# GPS_Tracker_V3.net
KiCad netlist of a schematic drawn in EAGLE
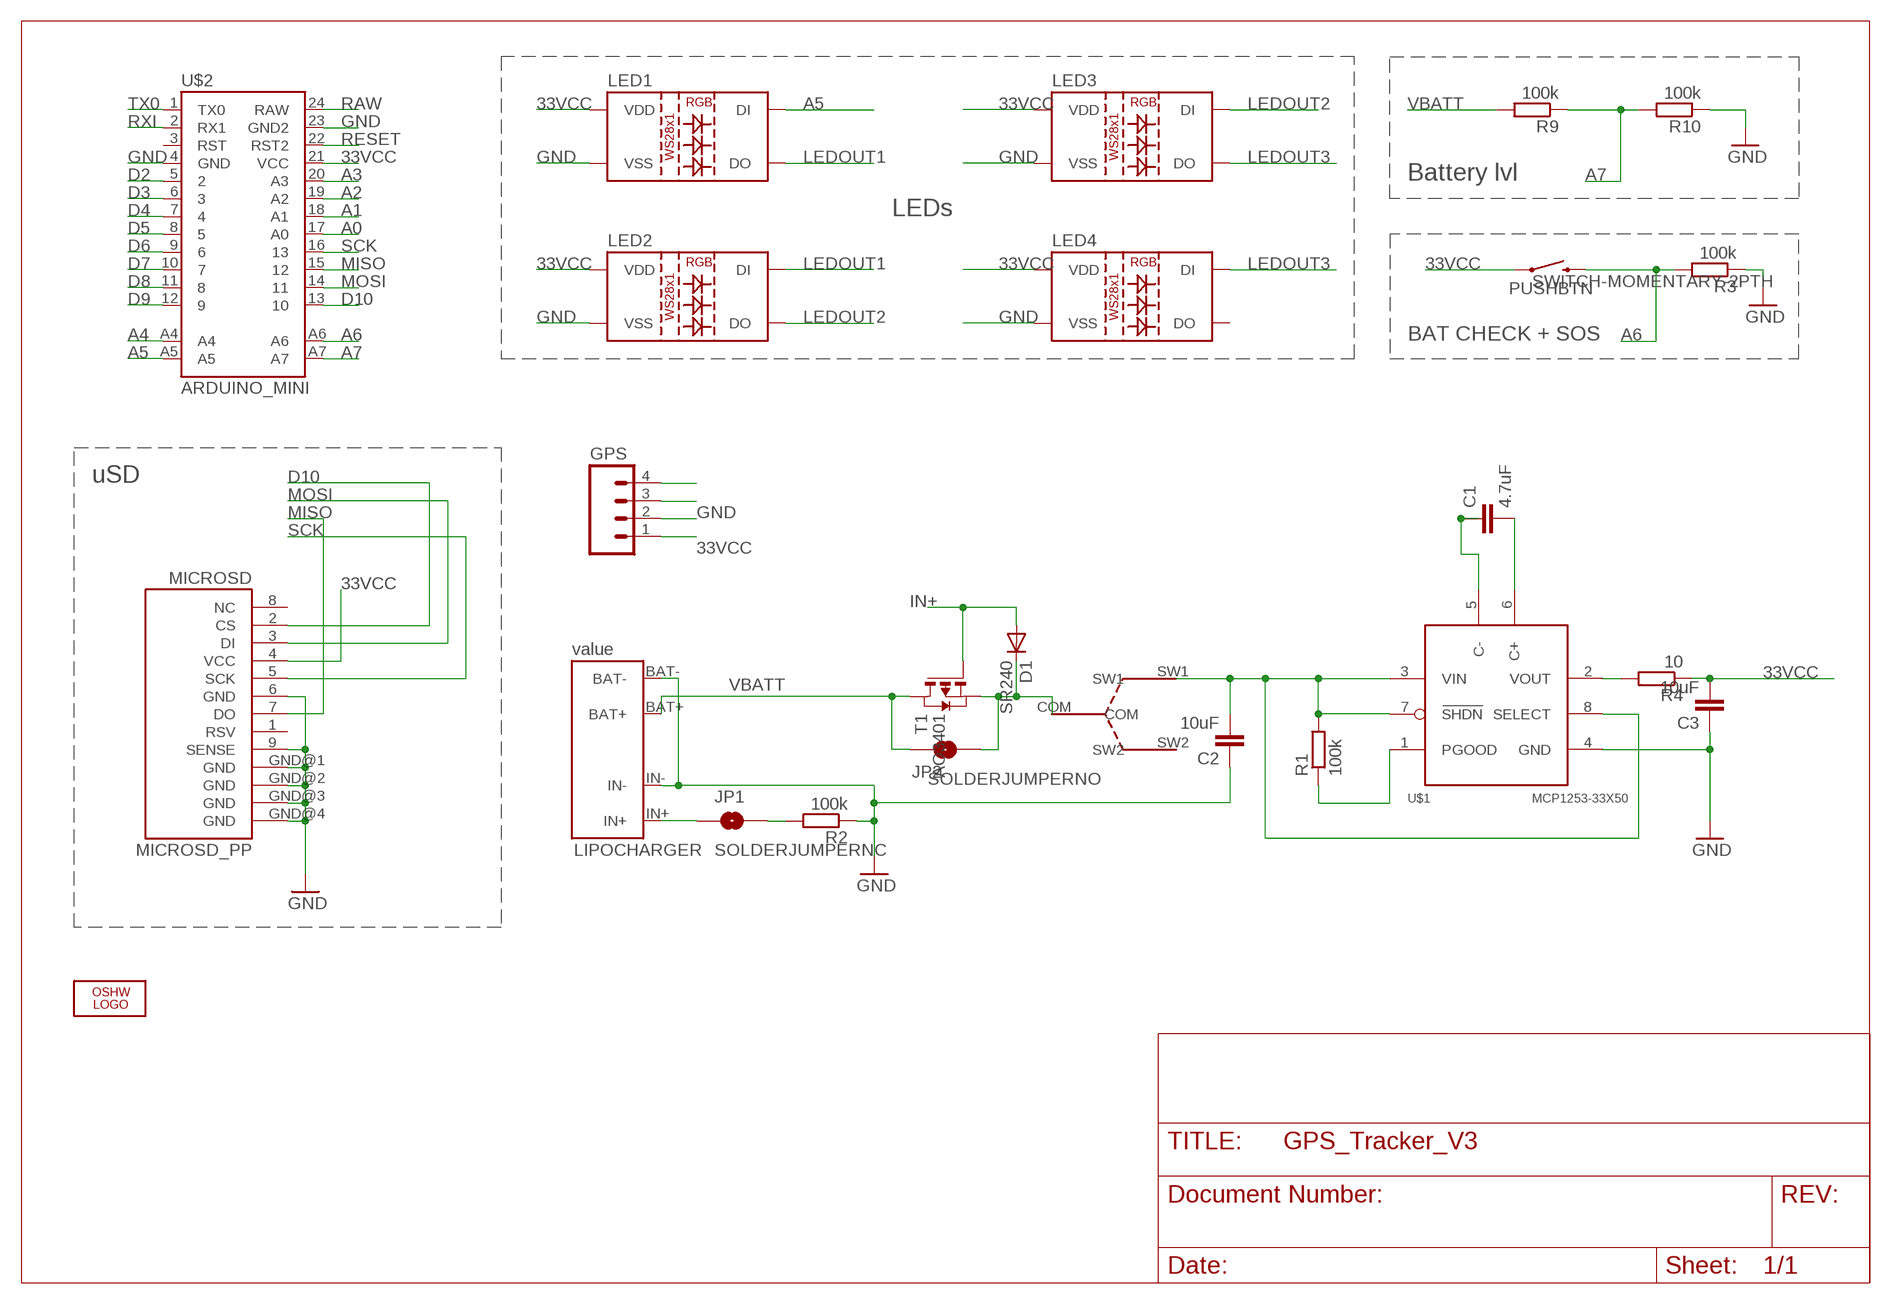
[diagram p0: schematic, sheet 1]

(export (version "E")
  (design (tool "Eeschema 10.0.6"))
  (components
    (comp (ref "C1")
      (value "4.7uF")
      (footprint "eagle-import:C1206")
      (libsource (lib "eagle-import") (part "C-EUC1206"))
    )
    (comp (ref "C2")
      (value "10uF")
      (footprint "eagle-import:C1206")
      (libsource (lib "eagle-import") (part "C-EUC1206"))
    )
    (comp (ref "C3")
      (value "10uF")
      (footprint "eagle-import:C1206")
      (libsource (lib "eagle-import") (part "C-EUC1206"))
    )
    (comp (ref "D1")
      (value "SR240")
      (footprint "eagle-import:DO214AC")
      (libsource (lib "eagle-import") (part "DIODE-DO214AC"))
    )
    (comp (ref "GPS")
      (value "M04PTH")
      (footprint "eagle-import:1X04")
      (libsource (lib "eagle-import") (part "M04PTH"))
    )
    (comp (ref "JP1")
      (value "SOLDERJUMPERNC")
      (footprint "eagle-import:SJ_2S")
      (libsource (lib "eagle-import") (part "SOLDERJUMPERNC"))
    )
    (comp (ref "JP2")
      (value "SOLDERJUMPERNO")
      (footprint "eagle-import:SJ_2S-NO")
      (libsource (lib "eagle-import") (part "SOLDERJUMPERNO"))
    )
    (comp (ref "LED1")
      (value "LED-TRICOLOR-5050-ICWS2811")
      (footprint "eagle-import:LED-TRICOLOR-5050-IC")
      (libsource (lib "eagle-import") (part "LED-TRICOLOR-5050-ICWS2811"))
    )
    (comp (ref "LED2")
      (value "LED-TRICOLOR-5050-ICWS2811")
      (footprint "eagle-import:LED-TRICOLOR-5050-IC")
      (libsource (lib "eagle-import") (part "LED-TRICOLOR-5050-ICWS2811"))
    )
    (comp (ref "LED3")
      (value "LED-TRICOLOR-5050-ICWS2811")
      (footprint "eagle-import:LED-TRICOLOR-5050-IC")
      (libsource (lib "eagle-import") (part "LED-TRICOLOR-5050-ICWS2811"))
    )
    (comp (ref "LED4")
      (value "LED-TRICOLOR-5050-ICWS2811")
      (footprint "eagle-import:LED-TRICOLOR-5050-IC")
      (libsource (lib "eagle-import") (part "LED-TRICOLOR-5050-ICWS2811"))
    )
    (comp (ref "LIPOCHARGER")
      (value "LIPO_CHARGER")
      (footprint "eagle-import:LIPO_CHARGER")
      (libsource (lib "eagle-import") (part "LIPO_CHARGER"))
    )
    (comp (ref "LOGO1")
      (value "OSHW_LOGO_10MILX0200-NT")
      (footprint "eagle-import:OSHW_10X200_NOTEXT")
      (libsource (lib "eagle-import") (part "OSHW_LOGO_10MILX0200-NT"))
    )
    (comp (ref "MICROSD")
      (value "MICROSD_PP")
      (footprint "eagle-import:MICROSD_PP")
      (libsource (lib "eagle-import") (part "MICROSD_PP"))
    )
    (comp (ref "PUSHBTN")
      (value "SWITCH-MOMENTARY-2PTH")
      (footprint "eagle-import:TACTILE-PTH")
      (libsource (lib "eagle-import") (part "SWITCH-MOMENTARY-2PTH"))
    )
    (comp (ref "R1")
      (value "100k")
      (footprint "eagle-import:R1206")
      (libsource (lib "eagle-import") (part "R-EU_R1206"))
    )
    (comp (ref "R2")
      (value "100k")
      (footprint "eagle-import:R1206")
      (libsource (lib "eagle-import") (part "R-EU_R1206"))
    )
    (comp (ref "R3")
      (value "100k")
      (footprint "eagle-import:R1206")
      (libsource (lib "eagle-import") (part "R-EU_R1206"))
    )
    (comp (ref "R4")
      (value "10")
      (footprint "eagle-import:R1206")
      (libsource (lib "eagle-import") (part "R-EU_R1206"))
    )
    (comp (ref "R9")
      (value "100k")
      (footprint "eagle-import:R1206")
      (libsource (lib "eagle-import") (part "R-EU_R1206"))
    )
    (comp (ref "R10")
      (value "100k")
      (footprint "eagle-import:R1206")
      (libsource (lib "eagle-import") (part "R-EU_R1206"))
    )
    (comp (ref "SW")
      (value "SWITCHDAV")
      (footprint "eagle-import:5IL3MM")
      (libsource (lib "eagle-import") (part "SWITCHDAV"))
    )
    (comp (ref "T1")
      (value "AO3401")
      (footprint "eagle-import:SOT-23")
      (libsource (lib "eagle-import") (part "PMOSSOT23"))
    )
    (comp (ref "U$1")
      (value "MCP1253-33X50")
      (footprint "eagle-import:MSOP8")
      (libsource (lib "eagle-import") (part "MCP1253-33X50"))
    )
    (comp (ref "U$2")
      (value "ARDUINO_MINI")
      (footprint "eagle-import:ARDUINO_MINI")
      (libsource (lib "eagle-import") (part "ARDUINO_MINI"))
    )
  )
  (nets
    (net (code "1") (name "/33VCC") (class "Default")
      (node (ref "C3") (pin "2") (pinfunction "2_2") (pintype "passive"))
      (node (ref "GPS") (pin "1") (pinfunction "1_1") (pintype "passive"))
      (node (ref "LED1") (pin "3") (pinfunction "VDD_3") (pintype "bidirectional"))
      (node (ref "LED1") (pin "5") (pinfunction "VDD_5") (pintype "bidirectional"))
      (node (ref "LED2") (pin "3") (pinfunction "VDD_3") (pintype "bidirectional"))
      (node (ref "LED2") (pin "5") (pinfunction "VDD_5") (pintype "bidirectional"))
      (node (ref "LED3") (pin "3") (pinfunction "VDD_3") (pintype "bidirectional"))
      (node (ref "LED3") (pin "5") (pinfunction "VDD_5") (pintype "bidirectional"))
      (node (ref "LED4") (pin "3") (pinfunction "VDD_3") (pintype "bidirectional"))
      (node (ref "LED4") (pin "5") (pinfunction "VDD_5") (pintype "bidirectional"))
      (node (ref "MICROSD") (pin "4") (pinfunction "VCC_4") (pintype "bidirectional"))
      (node (ref "PUSHBTN") (pin "1") (pinfunction "1_1") (pintype "passive"))
      (node (ref "R4") (pin "1") (pinfunction "1_1") (pintype "passive"))
      (node (ref "U$2") (pin "21") (pinfunction "VCC_21") (pintype "bidirectional"))
    )
    (net (code "2") (name "/A0") (class "Default")
      (node (ref "U$2") (pin "17") (pinfunction "A0_17") (pintype "bidirectional"))
    )
    (net (code "3") (name "/A1") (class "Default")
      (node (ref "U$2") (pin "18") (pinfunction "A1_18") (pintype "bidirectional"))
    )
    (net (code "4") (name "/A2") (class "Default")
      (node (ref "U$2") (pin "19") (pinfunction "A2_19") (pintype "bidirectional"))
    )
    (net (code "5") (name "/A3") (class "Default")
      (node (ref "U$2") (pin "20") (pinfunction "A3_20") (pintype "bidirectional"))
    )
    (net (code "6") (name "/A4") (class "Default")
      (node (ref "U$2") (pin "A4") (pinfunction "A4_A4") (pintype "bidirectional"))
    )
    (net (code "7") (name "/A5") (class "Default")
      (node (ref "LED1") (pin "2") (pinfunction "DI_2") (pintype "bidirectional"))
      (node (ref "U$2") (pin "A5") (pinfunction "A5_A5") (pintype "bidirectional"))
    )
    (net (code "8") (name "/A6") (class "Default")
      (node (ref "PUSHBTN") (pin "3") (pinfunction "2_3") (pintype "passive"))
      (node (ref "R3") (pin "2") (pinfunction "2_2") (pintype "passive"))
      (node (ref "U$2") (pin "A6") (pinfunction "A6_A6") (pintype "bidirectional"))
    )
    (net (code "9") (name "/A7") (class "Default")
      (node (ref "R10") (pin "2") (pinfunction "2_2") (pintype "passive"))
      (node (ref "R9") (pin "1") (pinfunction "1_1") (pintype "passive"))
      (node (ref "U$2") (pin "A7") (pinfunction "A7_A7") (pintype "bidirectional"))
    )
    (net (code "10") (name "/D2") (class "Default")
      (node (ref "U$2") (pin "5") (pinfunction "2_5") (pintype "bidirectional"))
    )
    (net (code "11") (name "/D3") (class "Default")
      (node (ref "U$2") (pin "6") (pinfunction "3_6") (pintype "bidirectional"))
    )
    (net (code "12") (name "/D4") (class "Default")
      (node (ref "U$2") (pin "7") (pinfunction "4_7") (pintype "bidirectional"))
    )
    (net (code "13") (name "/D5") (class "Default")
      (node (ref "U$2") (pin "8") (pinfunction "5_8") (pintype "bidirectional"))
    )
    (net (code "14") (name "/D6") (class "Default")
      (node (ref "U$2") (pin "9") (pinfunction "6_9") (pintype "bidirectional"))
    )
    (net (code "15") (name "/D7") (class "Default")
      (node (ref "U$2") (pin "10") (pinfunction "7_10") (pintype "bidirectional"))
    )
    (net (code "16") (name "/D8") (class "Default")
      (node (ref "U$2") (pin "11") (pinfunction "8_11") (pintype "bidirectional"))
    )
    (net (code "17") (name "/D9") (class "Default")
      (node (ref "U$2") (pin "12") (pinfunction "9_12") (pintype "bidirectional"))
    )
    (net (code "18") (name "/D10") (class "Default")
      (node (ref "MICROSD") (pin "2") (pinfunction "CS_2") (pintype "bidirectional"))
      (node (ref "U$2") (pin "13") (pinfunction "10_13") (pintype "bidirectional"))
    )
    (net (code "19") (name "/IN+") (class "Default")
      (node (ref "D1") (pin "A") (pinfunction "A_A") (pintype "passive"))
      (node (ref "JP1") (pin "2") (pinfunction "2_2") (pintype "passive"))
      (node (ref "R2") (pin "2") (pinfunction "2_2") (pintype "passive"))
      (node (ref "T1") (pin "3") (pinfunction "G_3") (pintype "passive"))
    )
    (net (code "20") (name "/LEDOUT1") (class "Default")
      (node (ref "LED1") (pin "1") (pinfunction "DO_1") (pintype "bidirectional"))
      (node (ref "LED2") (pin "2") (pinfunction "DI_2") (pintype "bidirectional"))
    )
    (net (code "21") (name "/LEDOUT2") (class "Default")
      (node (ref "LED2") (pin "1") (pinfunction "DO_1") (pintype "bidirectional"))
      (node (ref "LED3") (pin "2") (pinfunction "DI_2") (pintype "bidirectional"))
    )
    (net (code "22") (name "/LEDOUT3") (class "Default")
      (node (ref "LED3") (pin "1") (pinfunction "DO_1") (pintype "bidirectional"))
      (node (ref "LED4") (pin "2") (pinfunction "DI_2") (pintype "bidirectional"))
    )
    (net (code "23") (name "/MISO") (class "Default")
      (node (ref "MICROSD") (pin "7") (pinfunction "DO_7") (pintype "bidirectional"))
      (node (ref "U$2") (pin "15") (pinfunction "12_15") (pintype "bidirectional"))
    )
    (net (code "24") (name "/MOSI") (class "Default")
      (node (ref "MICROSD") (pin "3") (pinfunction "DI_3") (pintype "bidirectional"))
      (node (ref "U$2") (pin "14") (pinfunction "11_14") (pintype "bidirectional"))
    )
    (net (code "25") (name "/RAW") (class "Default")
      (node (ref "U$2") (pin "24") (pinfunction "RAW_24") (pintype "bidirectional"))
    )
    (net (code "26") (name "/RESET") (class "Default")
      (node (ref "U$2") (pin "22") (pinfunction "RST2_22") (pintype "bidirectional"))
    )
    (net (code "27") (name "/RXI") (class "Default")
      (node (ref "U$2") (pin "2") (pinfunction "RX1_2") (pintype "bidirectional"))
    )
    (net (code "28") (name "/SCK") (class "Default")
      (node (ref "MICROSD") (pin "5") (pinfunction "SCK_5") (pintype "bidirectional"))
      (node (ref "U$2") (pin "16") (pinfunction "13_16") (pintype "bidirectional"))
    )
    (net (code "29") (name "/TX0") (class "Default")
      (node (ref "U$2") (pin "1") (pinfunction "TX0_1") (pintype "bidirectional"))
    )
    (net (code "30") (name "/VBATT") (class "Default")
      (node (ref "JP2") (pin "1") (pinfunction "1_1") (pintype "passive"))
      (node (ref "LIPOCHARGER") (pin "BAT+") (pinfunction "BAT+_BAT+") (pintype "bidirectional"))
      (node (ref "R9") (pin "2") (pinfunction "2_2") (pintype "passive"))
      (node (ref "T1") (pin "1") (pinfunction "D_1") (pintype "passive"))
    )
    (net (code "31") (name "GND") (class "Default")
      (node (ref "C2") (pin "1") (pinfunction "1_1") (pintype "passive"))
      (node (ref "C3") (pin "1") (pinfunction "1_1") (pintype "passive"))
      (node (ref "GPS") (pin "2") (pinfunction "2_2") (pintype "passive"))
      (node (ref "LED1") (pin "6") (pinfunction "VSS_6") (pintype "bidirectional"))
      (node (ref "LED2") (pin "6") (pinfunction "VSS_6") (pintype "bidirectional"))
      (node (ref "LED3") (pin "6") (pinfunction "VSS_6") (pintype "bidirectional"))
      (node (ref "LED4") (pin "6") (pinfunction "VSS_6") (pintype "bidirectional"))
      (node (ref "LIPOCHARGER") (pin "BAT-") (pinfunction "BAT-_BAT-") (pintype "bidirectional"))
      (node (ref "LIPOCHARGER") (pin "IN-") (pinfunction "IN-_IN-") (pintype "bidirectional"))
      (node (ref "MICROSD") (pin "6") (pinfunction "GND_6") (pintype "bidirectional"))
      (node (ref "MICROSD") (pin "9") (pinfunction "SENSE_9") (pintype "bidirectional"))
      (node (ref "MICROSD") (pin "GND@1") (pinfunction "GND_GND@1") (pintype "bidirectional"))
      (node (ref "MICROSD") (pin "GND@2") (pinfunction "GND_GND@2") (pintype "bidirectional"))
      (node (ref "MICROSD") (pin "GND@3") (pinfunction "GND_GND@3") (pintype "bidirectional"))
      (node (ref "MICROSD") (pin "GND@4") (pinfunction "GND_GND@4") (pintype "bidirectional"))
      (node (ref "R10") (pin "1") (pinfunction "1_1") (pintype "passive"))
      (node (ref "R2") (pin "1") (pinfunction "1_1") (pintype "passive"))
      (node (ref "R3") (pin "1") (pinfunction "1_1") (pintype "passive"))
      (node (ref "U$1") (pin "4") (pinfunction "GND_4") (pintype "power_in"))
      (node (ref "U$2") (pin "23") (pinfunction "GND2_23") (pintype "bidirectional"))
      (node (ref "U$2") (pin "4") (pinfunction "GND_4") (pintype "bidirectional"))
    )
    (net (code "32") (name "Net-(JP1-Pad1)") (class "Default")
      (node (ref "JP1") (pin "1") (pinfunction "1_1") (pintype "passive"))
      (node (ref "LIPOCHARGER") (pin "IN+") (pinfunction "IN+_IN+") (pintype "bidirectional"))
    )
    (net (code "33") (name "Net-(T1-S)") (class "Default")
      (node (ref "D1") (pin "C") (pinfunction "C_C") (pintype "passive"))
      (node (ref "JP2") (pin "2") (pinfunction "2_2") (pintype "passive"))
      (node (ref "SW") (pin "COM") (pinfunction "COM_COM") (pintype "bidirectional"))
      (node (ref "T1") (pin "2") (pinfunction "S_2") (pintype "passive"))
    )
    (net (code "34") (name "Net-(U$1-C+)") (class "Default")
      (node (ref "C1") (pin "2") (pinfunction "2_2") (pintype "passive"))
      (node (ref "U$1") (pin "6") (pinfunction "C+_6") (pintype "bidirectional"))
    )
    (net (code "35") (name "Net-(U$1-C-)") (class "Default")
      (node (ref "C1") (pin "1") (pinfunction "1_1") (pintype "passive"))
      (node (ref "U$1") (pin "5") (pinfunction "C-_5") (pintype "bidirectional"))
    )
    (net (code "36") (name "Net-(U$1-PGOOD)") (class "Default")
      (node (ref "R1") (pin "1") (pinfunction "1_1") (pintype "passive"))
      (node (ref "U$1") (pin "1") (pinfunction "PGOOD_1") (pintype "output"))
    )
    (net (code "37") (name "Net-(U$1-SELECT)") (class "Default")
      (node (ref "C2") (pin "2") (pinfunction "2_2") (pintype "passive"))
      (node (ref "R1") (pin "2") (pinfunction "2_2") (pintype "passive"))
      (node (ref "SW") (pin "SW1") (pinfunction "SW1_SW1") (pintype "bidirectional"))
      (node (ref "U$1") (pin "3") (pinfunction "VIN_3") (pintype "power_in"))
      (node (ref "U$1") (pin "7") (pinfunction "SHDN_7") (pintype "input"))
      (node (ref "U$1") (pin "8") (pinfunction "SELECT_8") (pintype "input"))
    )
    (net (code "38") (name "Net-(U$1-VOUT)") (class "Default")
      (node (ref "R4") (pin "2") (pinfunction "2_2") (pintype "passive"))
      (node (ref "U$1") (pin "2") (pinfunction "VOUT_2") (pintype "output"))
    )
    (net (code "39") (name "unconnected-(GPS-Pad3)") (class "Default")
      (node (ref "GPS") (pin "3") (pinfunction "3_3") (pintype "passive"))
    )
    (net (code "40") (name "unconnected-(GPS-Pad4)") (class "Default")
      (node (ref "GPS") (pin "4") (pinfunction "4_4") (pintype "passive"))
    )
    (net (code "41") (name "unconnected-(LED4-DO-Pad1)") (class "Default")
      (node (ref "LED4") (pin "1") (pinfunction "DO_1") (pintype "bidirectional"))
    )
    (net (code "42") (name "unconnected-(MICROSD-NC-Pad8)") (class "Default")
      (node (ref "MICROSD") (pin "8") (pinfunction "NC_8") (pintype "bidirectional"))
    )
    (net (code "43") (name "unconnected-(MICROSD-RSV-Pad1)") (class "Default")
      (node (ref "MICROSD") (pin "1") (pinfunction "RSV_1") (pintype "bidirectional"))
    )
    (net (code "44") (name "unconnected-(SW-PadSW2)") (class "Default")
      (node (ref "SW") (pin "SW2") (pinfunction "SW2_SW2") (pintype "bidirectional"))
    )
    (net (code "45") (name "unconnected-(U$2-RST-Pad3)") (class "Default")
      (node (ref "U$2") (pin "3") (pinfunction "RST_3") (pintype "bidirectional"))
    )
  )
)
